# gpi-pwr.net
KiCad netlist of a schematic drawn in EAGLE
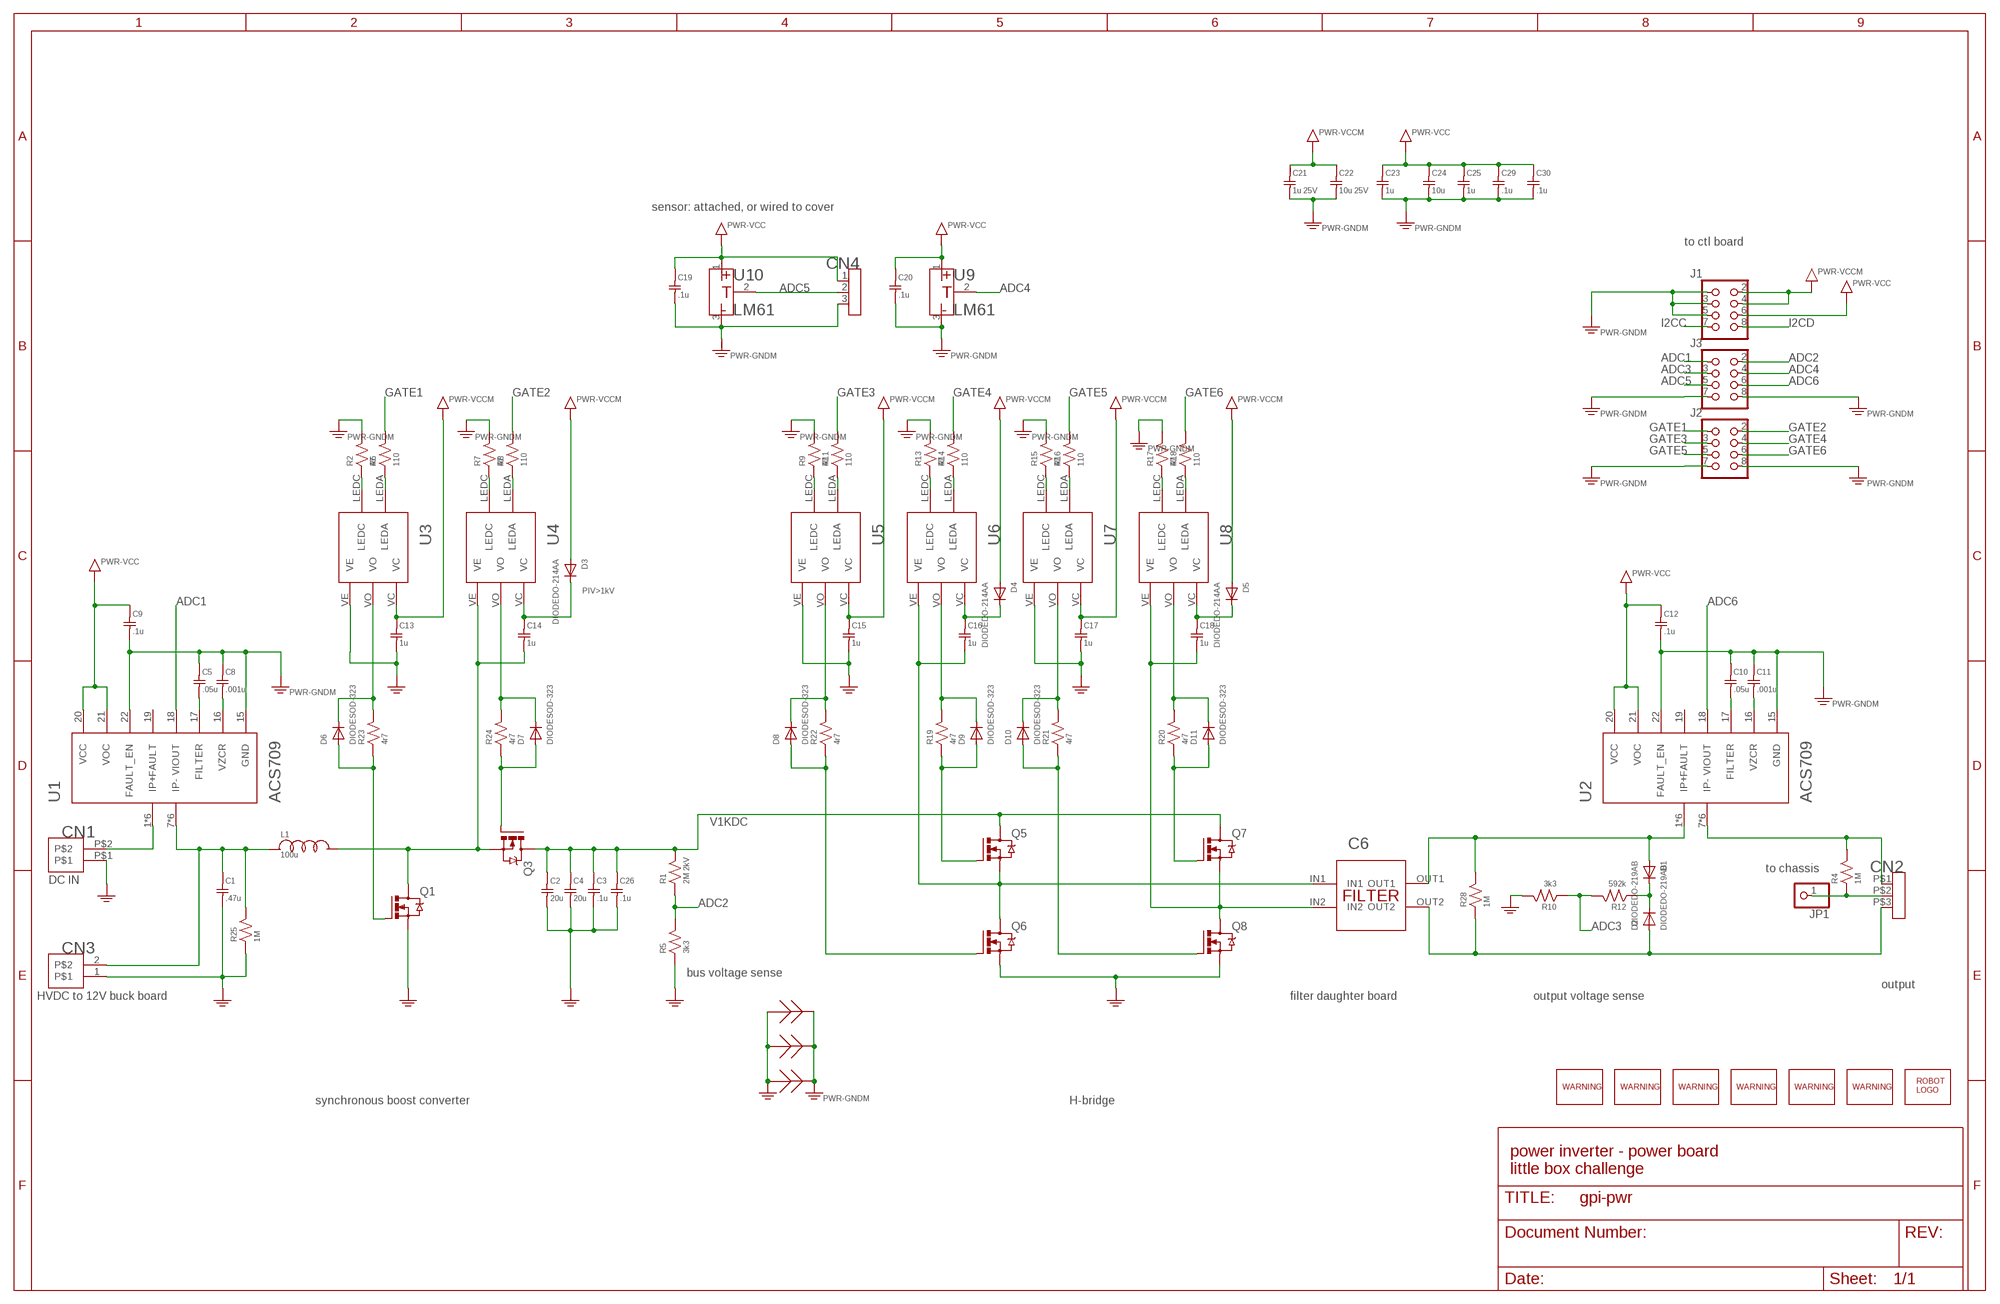
[diagram p0: schematic, sheet 1]

(export (version "E")
  (design (tool "Eeschema 10.0.6"))
  (components
    (comp (ref "C1")
      (value ".47u")
      (footprint "eagle-import:R46KI333000N1M")
      (libsource (lib "eagle-import") (part "CR46KI333000N1M"))
    )
    (comp (ref "C2")
      (value "20u")
      (footprint "eagle-import:MKP1848S62010JY5F")
      (libsource (lib "eagle-import") (part "CMKP1848S62010JY5F"))
    )
    (comp (ref "C3")
      (value ".1u")
      (footprint "eagle-import:SMD2220")
      (libsource (lib "eagle-import") (part "C2220"))
    )
    (comp (ref "C4")
      (value "20u")
      (footprint "eagle-import:MKP1848S62010JY5F")
      (libsource (lib "eagle-import") (part "CMKP1848S62010JY5F"))
    )
    (comp (ref "C5")
      (value ".05u")
      (footprint "eagle-import:SMD0603")
      (libsource (lib "eagle-import") (part "C0603"))
    )
    (comp (ref "C6")
      (value "FILTER")
      (footprint "eagle-import:FILTER-B4R0")
      (libsource (lib "eagle-import") (part "FILTER"))
    )
    (comp (ref "C8")
      (value ".001u")
      (footprint "eagle-import:SMD0603")
      (libsource (lib "eagle-import") (part "C0603"))
    )
    (comp (ref "C9")
      (value ".1u")
      (footprint "eagle-import:SMD0603")
      (libsource (lib "eagle-import") (part "C0603"))
    )
    (comp (ref "C10")
      (value ".05u")
      (footprint "eagle-import:SMD0603")
      (libsource (lib "eagle-import") (part "C0603"))
    )
    (comp (ref "C11")
      (value ".001u")
      (footprint "eagle-import:SMD0603")
      (libsource (lib "eagle-import") (part "C0603"))
    )
    (comp (ref "C12")
      (value ".1u")
      (footprint "eagle-import:SMD0603")
      (libsource (lib "eagle-import") (part "C0603"))
    )
    (comp (ref "C13")
      (value "1u")
      (footprint "eagle-import:SMD0603")
      (libsource (lib "eagle-import") (part "C0603"))
    )
    (comp (ref "C14")
      (value "1u")
      (footprint "eagle-import:SMD0603")
      (libsource (lib "eagle-import") (part "C0603"))
    )
    (comp (ref "C15")
      (value "1u")
      (footprint "eagle-import:SMD0603")
      (libsource (lib "eagle-import") (part "C0603"))
    )
    (comp (ref "C16")
      (value "1u")
      (footprint "eagle-import:SMD0603")
      (libsource (lib "eagle-import") (part "C0603"))
    )
    (comp (ref "C17")
      (value "1u")
      (footprint "eagle-import:SMD0603")
      (libsource (lib "eagle-import") (part "C0603"))
    )
    (comp (ref "C18")
      (value "1u")
      (footprint "eagle-import:SMD0603")
      (libsource (lib "eagle-import") (part "C0603"))
    )
    (comp (ref "C19")
      (value ".1u")
      (footprint "eagle-import:SMD0603")
      (libsource (lib "eagle-import") (part "C0603"))
    )
    (comp (ref "C20")
      (value ".1u")
      (footprint "eagle-import:SMD0603")
      (libsource (lib "eagle-import") (part "C0603"))
    )
    (comp (ref "C21")
      (value "1u 25V")
      (footprint "eagle-import:SMD0603")
      (libsource (lib "eagle-import") (part "C0603"))
    )
    (comp (ref "C22")
      (value "10u 25V")
      (footprint "eagle-import:SMD0603")
      (libsource (lib "eagle-import") (part "C0603"))
    )
    (comp (ref "C23")
      (value "1u")
      (footprint "eagle-import:SMD0603")
      (libsource (lib "eagle-import") (part "C0603"))
    )
    (comp (ref "C24")
      (value "10u")
      (footprint "eagle-import:SMD0603")
      (libsource (lib "eagle-import") (part "C0603"))
    )
    (comp (ref "C25")
      (value "1u")
      (footprint "eagle-import:SMD0603")
      (libsource (lib "eagle-import") (part "C0603"))
    )
    (comp (ref "C26")
      (value ".1u")
      (footprint "eagle-import:SMD2220")
      (libsource (lib "eagle-import") (part "C2220"))
    )
    (comp (ref "C29")
      (value ".1u")
      (footprint "eagle-import:SMD0603")
      (libsource (lib "eagle-import") (part "C0603"))
    )
    (comp (ref "C30")
      (value ".1u")
      (footprint "eagle-import:SMD0603")
      (libsource (lib "eagle-import") (part "C0603"))
    )
    (comp (ref "CN1")
      (value "HEADER-1X2")
      (footprint "eagle-import:CONN-10AWG-2")
      (libsource (lib "eagle-import") (part "HEADER-1X2"))
    )
    (comp (ref "CN2")
      (value "HEADER-3X1")
      (footprint "eagle-import:CONN-10AWG-3")
      (libsource (lib "eagle-import") (part "HEADER-3X1"))
    )
    (comp (ref "CN3")
      (value "HEADER-1X2.4")
      (footprint "eagle-import:HEADER-1X2-THM-WIDE")
      (libsource (lib "eagle-import") (part "HEADER-1X2.4"))
    )
    (comp (ref "CN4")
      (value "HEADER-3X12MM")
      (footprint "eagle-import:HEADER-3X1-2SMD")
      (libsource (lib "eagle-import") (part "HEADER-3X12MM"))
    )
    (comp (ref "D1")
      (value "DIODEDO-219AB")
      (footprint "eagle-import:DO-219AB")
      (libsource (lib "eagle-import") (part "DIODEDO-219AB"))
    )
    (comp (ref "D2")
      (value "DIODEDO-219AB")
      (footprint "eagle-import:DO-219AB")
      (libsource (lib "eagle-import") (part "DIODEDO-219AB"))
    )
    (comp (ref "D3")
      (value "DIODEDO-214AA")
      (footprint "eagle-import:DO-214AA")
      (libsource (lib "eagle-import") (part "DIODEDO-214AA"))
    )
    (comp (ref "D4")
      (value "DIODEDO-214AA")
      (footprint "eagle-import:DO-214AA")
      (libsource (lib "eagle-import") (part "DIODEDO-214AA"))
    )
    (comp (ref "D5")
      (value "DIODEDO-214AA")
      (footprint "eagle-import:DO-214AA")
      (libsource (lib "eagle-import") (part "DIODEDO-214AA"))
    )
    (comp (ref "D6")
      (value "DIODESOD-323")
      (footprint "eagle-import:SOD-323")
      (libsource (lib "eagle-import") (part "DIODESOD-323"))
    )
    (comp (ref "D7")
      (value "DIODESOD-323")
      (footprint "eagle-import:SOD-323")
      (libsource (lib "eagle-import") (part "DIODESOD-323"))
    )
    (comp (ref "D8")
      (value "DIODESOD-323")
      (footprint "eagle-import:SOD-323")
      (libsource (lib "eagle-import") (part "DIODESOD-323"))
    )
    (comp (ref "D9")
      (value "DIODESOD-323")
      (footprint "eagle-import:SOD-323")
      (libsource (lib "eagle-import") (part "DIODESOD-323"))
    )
    (comp (ref "D10")
      (value "DIODESOD-323")
      (footprint "eagle-import:SOD-323")
      (libsource (lib "eagle-import") (part "DIODESOD-323"))
    )
    (comp (ref "D11")
      (value "DIODESOD-323")
      (footprint "eagle-import:SOD-323")
      (libsource (lib "eagle-import") (part "DIODESOD-323"))
    )
    (comp (ref "J1")
      (value "HEADER-2X4")
      (footprint "eagle-import:HEADER-2X04")
      (libsource (lib "eagle-import") (part "HEADER-2X4"))
    )
    (comp (ref "J2")
      (value "HEADER-2X4")
      (footprint "eagle-import:HEADER-2X04")
      (libsource (lib "eagle-import") (part "HEADER-2X4"))
    )
    (comp (ref "J3")
      (value "HEADER-2X4")
      (footprint "eagle-import:HEADER-2X04")
      (libsource (lib "eagle-import") (part "HEADER-2X4"))
    )
    (comp (ref "JP1")
      (value "PINHD-1X1")
      (footprint "eagle-import:1X01")
      (libsource (lib "eagle-import") (part "PINHD-1X1"))
    )
    (comp (ref "L1")
      (value "100u")
      (footprint "eagle-import:AIRD03")
      (libsource (lib "eagle-import") (part "LAIRD03"))
    )
    (comp (ref "Q1")
      (value "C2M0160120D")
      (footprint "eagle-import:TO-247-3-DOWN")
      (libsource (lib "eagle-import") (part "MOSFETTO247REV"))
    )
    (comp (ref "Q3")
      (value "C2M0160120D")
      (footprint "eagle-import:TO-247-3-DOWN")
      (libsource (lib "eagle-import") (part "MOSFETTO247REV"))
    )
    (comp (ref "Q5")
      (value "C2M0160120D")
      (footprint "eagle-import:TO-247-3-DOWN")
      (libsource (lib "eagle-import") (part "MOSFETTO247REV"))
    )
    (comp (ref "Q6")
      (value "C2M0160120D")
      (footprint "eagle-import:TO-247-3-DOWN")
      (libsource (lib "eagle-import") (part "MOSFETTO247REV"))
    )
    (comp (ref "Q7")
      (value "C2M0160120D")
      (footprint "eagle-import:TO-247-3-DOWN")
      (libsource (lib "eagle-import") (part "MOSFETTO247REV"))
    )
    (comp (ref "Q8")
      (value "C2M0160120D")
      (footprint "eagle-import:TO-247-3-DOWN")
      (libsource (lib "eagle-import") (part "MOSFETTO247REV"))
    )
    (comp (ref "R1")
      (value "2M 2kV")
      (footprint "eagle-import:SMD2512")
      (libsource (lib "eagle-import") (part "R2512"))
    )
    (comp (ref "R2")
      (value "47")
      (footprint "eagle-import:SMD0603")
      (libsource (lib "eagle-import") (part "R0603"))
    )
    (comp (ref "R4")
      (value "1M")
      (footprint "eagle-import:SMD1206")
      (libsource (lib "eagle-import") (part "R1206"))
    )
    (comp (ref "R5")
      (value "3k3")
      (footprint "eagle-import:SMD0603")
      (libsource (lib "eagle-import") (part "R0603"))
    )
    (comp (ref "R6")
      (value "110")
      (footprint "eagle-import:SMD0603")
      (libsource (lib "eagle-import") (part "R0603"))
    )
    (comp (ref "R7")
      (value "47")
      (footprint "eagle-import:SMD0603")
      (libsource (lib "eagle-import") (part "R0603"))
    )
    (comp (ref "R8")
      (value "110")
      (footprint "eagle-import:SMD0603")
      (libsource (lib "eagle-import") (part "R0603"))
    )
    (comp (ref "R9")
      (value "47")
      (footprint "eagle-import:SMD0603")
      (libsource (lib "eagle-import") (part "R0603"))
    )
    (comp (ref "R10")
      (value "3k3")
      (footprint "eagle-import:SMD0603")
      (libsource (lib "eagle-import") (part "R0603"))
    )
    (comp (ref "R11")
      (value "110")
      (footprint "eagle-import:SMD0603")
      (libsource (lib "eagle-import") (part "R0603"))
    )
    (comp (ref "R12")
      (value "592k")
      (footprint "eagle-import:SMD1206")
      (libsource (lib "eagle-import") (part "R1206"))
    )
    (comp (ref "R13")
      (value "47")
      (footprint "eagle-import:SMD0603")
      (libsource (lib "eagle-import") (part "R0603"))
    )
    (comp (ref "R14")
      (value "110")
      (footprint "eagle-import:SMD0603")
      (libsource (lib "eagle-import") (part "R0603"))
    )
    (comp (ref "R15")
      (value "47")
      (footprint "eagle-import:SMD0603")
      (libsource (lib "eagle-import") (part "R0603"))
    )
    (comp (ref "R16")
      (value "110")
      (footprint "eagle-import:SMD0603")
      (libsource (lib "eagle-import") (part "R0603"))
    )
    (comp (ref "R17")
      (value "47")
      (footprint "eagle-import:SMD0603")
      (libsource (lib "eagle-import") (part "R0603"))
    )
    (comp (ref "R18")
      (value "110")
      (footprint "eagle-import:SMD0603")
      (libsource (lib "eagle-import") (part "R0603"))
    )
    (comp (ref "R19")
      (value "4r7")
      (footprint "eagle-import:SMD0508")
      (libsource (lib "eagle-import") (part "RSMD0508"))
    )
    (comp (ref "R20")
      (value "4r7")
      (footprint "eagle-import:SMD0508")
      (libsource (lib "eagle-import") (part "RSMD0508"))
    )
    (comp (ref "R21")
      (value "4r7")
      (footprint "eagle-import:SMD0508")
      (libsource (lib "eagle-import") (part "RSMD0508"))
    )
    (comp (ref "R22")
      (value "4r7")
      (footprint "eagle-import:SMD0508")
      (libsource (lib "eagle-import") (part "RSMD0508"))
    )
    (comp (ref "R23")
      (value "4r7")
      (footprint "eagle-import:SMD0508")
      (libsource (lib "eagle-import") (part "RSMD0508"))
    )
    (comp (ref "R24")
      (value "4r7")
      (footprint "eagle-import:SMD0508")
      (libsource (lib "eagle-import") (part "RSMD0508"))
    )
    (comp (ref "R25")
      (value "1M")
      (footprint "eagle-import:SMD1206")
      (libsource (lib "eagle-import") (part "R1206"))
    )
    (comp (ref "R28")
      (value "1M")
      (footprint "eagle-import:SMD1206")
      (libsource (lib "eagle-import") (part "R1206"))
    )
    (comp (ref "U$1")
      (value "ROBOTMAN-LOGO")
      (footprint "eagle-import:ROBOTMAN-LOGO")
      (libsource (lib "eagle-import") (part "ROBOTMAN-LOGO"))
    )
    (comp (ref "U$2")
      (value "SYMBOL-WARNING")
      (footprint "eagle-import:SYMBOL-WARNING")
      (libsource (lib "eagle-import") (part "SYMBOL-WARNING"))
    )
    (comp (ref "U$3")
      (value "SYMBOL-WARNING")
      (footprint "eagle-import:SYMBOL-WARNING")
      (libsource (lib "eagle-import") (part "SYMBOL-WARNING"))
    )
    (comp (ref "U$4")
      (value "SYMBOL-WARNING")
      (footprint "eagle-import:SYMBOL-WARNING")
      (libsource (lib "eagle-import") (part "SYMBOL-WARNING"))
    )
    (comp (ref "U$5")
      (value "SYMBOL-WARNING")
      (footprint "eagle-import:SYMBOL-WARNING")
      (libsource (lib "eagle-import") (part "SYMBOL-WARNING"))
    )
    (comp (ref "U$6")
      (value "SYMBOL-WARNING")
      (footprint "eagle-import:SYMBOL-WARNING")
      (libsource (lib "eagle-import") (part "SYMBOL-WARNING"))
    )
    (comp (ref "U$7")
      (value "SYMBOL-WARNING")
      (footprint "eagle-import:SYMBOL-WARNING")
      (libsource (lib "eagle-import") (part "SYMBOL-WARNING"))
    )
    (comp (ref "U1")
      (value "ACS709")
      (footprint "eagle-import:QSOP24")
      (libsource (lib "eagle-import") (part "ACS709"))
    )
    (comp (ref "U2")
      (value "ACS709")
      (footprint "eagle-import:QSOP24")
      (libsource (lib "eagle-import") (part "ACS709"))
    )
    (comp (ref "U3")
      (value "ACPL-P346P346")
      (footprint "eagle-import:ACPL-P346")
      (libsource (lib "eagle-import") (part "ACPL-P346P346"))
    )
    (comp (ref "U4")
      (value "ACPL-P346P346")
      (footprint "eagle-import:ACPL-P346")
      (libsource (lib "eagle-import") (part "ACPL-P346P346"))
    )
    (comp (ref "U5")
      (value "ACPL-P346P346")
      (footprint "eagle-import:ACPL-P346")
      (libsource (lib "eagle-import") (part "ACPL-P346P346"))
    )
    (comp (ref "U6")
      (value "ACPL-P346P346")
      (footprint "eagle-import:ACPL-P346")
      (libsource (lib "eagle-import") (part "ACPL-P346P346"))
    )
    (comp (ref "U7")
      (value "ACPL-P346P346")
      (footprint "eagle-import:ACPL-P346")
      (libsource (lib "eagle-import") (part "ACPL-P346P346"))
    )
    (comp (ref "U8")
      (value "ACPL-P346P346")
      (footprint "eagle-import:ACPL-P346")
      (libsource (lib "eagle-import") (part "ACPL-P346P346"))
    )
    (comp (ref "U9")
      (value "LM61")
      (footprint "eagle-import:SOT-23")
      (libsource (lib "eagle-import") (part "TEMPERATURE"))
    )
    (comp (ref "U10")
      (value "LM61")
      (footprint "eagle-import:SOT-23")
      (libsource (lib "eagle-import") (part "TEMPERATURE"))
    )
    (comp (ref "Z1")
      (value "SHORT")
      (footprint "eagle-import:SHORT")
      (libsource (lib "eagle-import") (part "SHORT"))
    )
    (comp (ref "Z2")
      (value "SHORT")
      (footprint "eagle-import:SHORT")
      (libsource (lib "eagle-import") (part "SHORT"))
    )
    (comp (ref "Z3")
      (value "SHORT")
      (footprint "eagle-import:SHORT")
      (libsource (lib "eagle-import") (part "SHORT"))
    )
  )
  (nets
    (net (code "1") (name "/ADC1") (class "Default")
      (node (ref "J3") (pin "1") (pinfunction "P$1_1") (pintype "passive"))
      (node (ref "U1") (pin "18") (pinfunction "VIOUT_18") (pintype "bidirectional"))
    )
    (net (code "2") (name "/ADC2") (class "Default")
      (node (ref "J3") (pin "2") (pinfunction "P$2_2") (pintype "passive"))
      (node (ref "R1") (pin "P$1") (pinfunction "P$1_P$1") (pintype "passive"))
      (node (ref "R5") (pin "2") (pinfunction "P$2_2") (pintype "passive"))
    )
    (net (code "3") (name "/ADC3") (class "Default")
      (node (ref "J3") (pin "3") (pinfunction "P$3_3") (pintype "passive"))
      (node (ref "R10") (pin "1") (pinfunction "P$1_1") (pintype "passive"))
      (node (ref "R12") (pin "2") (pinfunction "P$2_2") (pintype "passive"))
    )
    (net (code "4") (name "/ADC4") (class "Default")
      (node (ref "J3") (pin "4") (pinfunction "P$4_4") (pintype "passive"))
      (node (ref "U9") (pin "2") (pinfunction "OUT_2") (pintype "bidirectional"))
    )
    (net (code "5") (name "/ADC5") (class "Default")
      (node (ref "CN4") (pin "2") (pinfunction "2_2") (pintype "bidirectional"))
      (node (ref "J3") (pin "5") (pinfunction "P$5_5") (pintype "passive"))
      (node (ref "U10") (pin "2") (pinfunction "OUT_2") (pintype "bidirectional"))
    )
    (net (code "6") (name "/ADC6") (class "Default")
      (node (ref "J3") (pin "6") (pinfunction "P$6_6") (pintype "passive"))
      (node (ref "U2") (pin "18") (pinfunction "VIOUT_18") (pintype "bidirectional"))
    )
    (net (code "7") (name "/GATE1") (class "Default")
      (node (ref "J2") (pin "1") (pinfunction "P$1_1") (pintype "passive"))
      (node (ref "R6") (pin "2") (pinfunction "P$2_2") (pintype "passive"))
    )
    (net (code "8") (name "/GATE2") (class "Default")
      (node (ref "J2") (pin "2") (pinfunction "P$2_2") (pintype "passive"))
      (node (ref "R8") (pin "2") (pinfunction "P$2_2") (pintype "passive"))
    )
    (net (code "9") (name "/GATE3") (class "Default")
      (node (ref "J2") (pin "3") (pinfunction "P$3_3") (pintype "passive"))
      (node (ref "R11") (pin "2") (pinfunction "P$2_2") (pintype "passive"))
    )
    (net (code "10") (name "/GATE4") (class "Default")
      (node (ref "J2") (pin "4") (pinfunction "P$4_4") (pintype "passive"))
      (node (ref "R14") (pin "2") (pinfunction "P$2_2") (pintype "passive"))
    )
    (net (code "11") (name "/GATE5") (class "Default")
      (node (ref "J2") (pin "5") (pinfunction "P$5_5") (pintype "passive"))
      (node (ref "R16") (pin "2") (pinfunction "P$2_2") (pintype "passive"))
    )
    (net (code "12") (name "/GATE6") (class "Default")
      (node (ref "J2") (pin "6") (pinfunction "P$6_6") (pintype "passive"))
      (node (ref "R18") (pin "2") (pinfunction "P$2_2") (pintype "passive"))
    )
    (net (code "13") (name "/I2CC") (class "Default")
      (node (ref "J1") (pin "7") (pinfunction "P$7_7") (pintype "passive"))
    )
    (net (code "14") (name "/I2CD") (class "Default")
      (node (ref "J1") (pin "8") (pinfunction "P$8_8") (pintype "passive"))
    )
    (net (code "15") (name "/V1KDC") (class "Default")
      (node (ref "C2") (pin "1A") (pinfunction "P$1_1A") (pintype "passive"))
      (node (ref "C2") (pin "1B") (pinfunction "P$1_1B") (pintype "passive"))
      (node (ref "C26") (pin "P$1") (pinfunction "P$1_P$1") (pintype "passive"))
      (node (ref "C3") (pin "P$1") (pinfunction "P$1_P$1") (pintype "passive"))
      (node (ref "C4") (pin "1A") (pinfunction "P$1_1A") (pintype "passive"))
      (node (ref "C4") (pin "1B") (pinfunction "P$1_1B") (pintype "passive"))
      (node (ref "Q3") (pin "2") (pinfunction "D_2") (pintype "passive"))
      (node (ref "Q5") (pin "2") (pinfunction "D_2") (pintype "passive"))
      (node (ref "Q7") (pin "2") (pinfunction "D_2") (pintype "passive"))
      (node (ref "R1") (pin "P$2") (pinfunction "P$2_P$2") (pintype "passive"))
    )
    (net (code "16") (name "Net-(C5-P$2)") (class "Default")
      (node (ref "C5") (pin "2") (pinfunction "P$2_2") (pintype "passive"))
      (node (ref "U1") (pin "17") (pinfunction "FILTER_17") (pintype "bidirectional"))
    )
    (net (code "17") (name "Net-(C8-P$2)") (class "Default")
      (node (ref "C8") (pin "2") (pinfunction "P$2_2") (pintype "passive"))
      (node (ref "U1") (pin "16") (pinfunction "VZCR_16") (pintype "bidirectional"))
    )
    (net (code "18") (name "Net-(C10-P$2)") (class "Default")
      (node (ref "C10") (pin "2") (pinfunction "P$2_2") (pintype "passive"))
      (node (ref "U2") (pin "17") (pinfunction "FILTER_17") (pintype "bidirectional"))
    )
    (net (code "19") (name "Net-(C11-P$2)") (class "Default")
      (node (ref "C11") (pin "2") (pinfunction "P$2_2") (pintype "passive"))
      (node (ref "U2") (pin "16") (pinfunction "VZCR_16") (pintype "bidirectional"))
    )
    (net (code "20") (name "Net-(C14-P$1)") (class "Default")
      (node (ref "C14") (pin "1") (pinfunction "P$1_1") (pintype "passive"))
      (node (ref "D3") (pin "C") (pinfunction "C_C") (pintype "passive"))
      (node (ref "U4") (pin "VC") (pinfunction "VC_VC") (pintype "bidirectional"))
    )
    (net (code "21") (name "Net-(C14-P$2)") (class "Default")
      (node (ref "C14") (pin "2") (pinfunction "P$2_2") (pintype "passive"))
      (node (ref "L1") (pin "P$2") (pinfunction "P$2_P$2") (pintype "passive"))
      (node (ref "Q1") (pin "2") (pinfunction "D_2") (pintype "passive"))
      (node (ref "Q3") (pin "3") (pinfunction "S_3") (pintype "passive"))
      (node (ref "U4") (pin "VE") (pinfunction "VE_VE") (pintype "bidirectional"))
    )
    (net (code "22") (name "Net-(C16-P$1)") (class "Default")
      (node (ref "C16") (pin "1") (pinfunction "P$1_1") (pintype "passive"))
      (node (ref "D4") (pin "C") (pinfunction "C_C") (pintype "passive"))
      (node (ref "U6") (pin "VC") (pinfunction "VC_VC") (pintype "bidirectional"))
    )
    (net (code "23") (name "Net-(C16-P$2)") (class "Default")
      (node (ref "C16") (pin "2") (pinfunction "P$2_2") (pintype "passive"))
      (node (ref "C6") (pin "IN1") (pinfunction "IN1_IN1") (pintype "bidirectional"))
      (node (ref "Q5") (pin "3") (pinfunction "S_3") (pintype "passive"))
      (node (ref "Q6") (pin "2") (pinfunction "D_2") (pintype "passive"))
      (node (ref "U6") (pin "VE") (pinfunction "VE_VE") (pintype "bidirectional"))
    )
    (net (code "24") (name "Net-(C18-P$1)") (class "Default")
      (node (ref "C18") (pin "1") (pinfunction "P$1_1") (pintype "passive"))
      (node (ref "D5") (pin "C") (pinfunction "C_C") (pintype "passive"))
      (node (ref "U8") (pin "VC") (pinfunction "VC_VC") (pintype "bidirectional"))
    )
    (net (code "25") (name "Net-(C18-P$2)") (class "Default")
      (node (ref "C18") (pin "2") (pinfunction "P$2_2") (pintype "passive"))
      (node (ref "C6") (pin "IN2") (pinfunction "IN2_IN2") (pintype "bidirectional"))
      (node (ref "Q7") (pin "3") (pinfunction "S_3") (pintype "passive"))
      (node (ref "Q8") (pin "2") (pinfunction "D_2") (pintype "passive"))
      (node (ref "U8") (pin "VE") (pinfunction "VE_VE") (pintype "bidirectional"))
    )
    (net (code "26") (name "Net-(CN1-PadP$2)") (class "Default")
      (node (ref "CN1") (pin "P$2") (pinfunction "P$2_P$2") (pintype "bidirectional"))
      (node (ref "U1") (pin "1") (pinfunction "IP+_1") (pintype "bidirectional"))
      (node (ref "U1") (pin "2") (pinfunction "IP+_2") (pintype "bidirectional"))
      (node (ref "U1") (pin "3") (pinfunction "IP+_3") (pintype "bidirectional"))
      (node (ref "U1") (pin "4") (pinfunction "IP+_4") (pintype "bidirectional"))
      (node (ref "U1") (pin "5") (pinfunction "IP+_5") (pintype "bidirectional"))
      (node (ref "U1") (pin "6") (pinfunction "IP+_6") (pintype "bidirectional"))
    )
    (net (code "27") (name "Net-(CN2-1)") (class "Default")
      (node (ref "CN2") (pin "P$1") (pinfunction "1_P$1") (pintype "bidirectional"))
      (node (ref "R4") (pin "2") (pinfunction "P$2_2") (pintype "passive"))
      (node (ref "U2") (pin "10") (pinfunction "IP-_10") (pintype "bidirectional"))
      (node (ref "U2") (pin "11") (pinfunction "IP-_11") (pintype "bidirectional"))
      (node (ref "U2") (pin "12") (pinfunction "IP-_12") (pintype "bidirectional"))
      (node (ref "U2") (pin "7") (pinfunction "IP-_7") (pintype "bidirectional"))
      (node (ref "U2") (pin "8") (pinfunction "IP-_8") (pintype "bidirectional"))
      (node (ref "U2") (pin "9") (pinfunction "IP-_9") (pintype "bidirectional"))
    )
    (net (code "28") (name "Net-(CN2-2)") (class "Default")
      (node (ref "CN2") (pin "P$2") (pinfunction "2_P$2") (pintype "bidirectional"))
      (node (ref "JP1") (pin "1") (pinfunction "1_1") (pintype "passive"))
      (node (ref "R4") (pin "1") (pinfunction "P$1_1") (pintype "passive"))
    )
    (net (code "29") (name "Net-(CN2-3)") (class "Default")
      (node (ref "C6") (pin "OUT2") (pinfunction "OUT2_OUT2") (pintype "bidirectional"))
      (node (ref "CN2") (pin "P$3") (pinfunction "3_P$3") (pintype "bidirectional"))
      (node (ref "D2") (pin "A") (pinfunction "A_A") (pintype "passive"))
      (node (ref "R28") (pin "1") (pinfunction "P$1_1") (pintype "passive"))
    )
    (net (code "30") (name "Net-(CN3-P$2)") (class "Default")
      (node (ref "C1") (pin "P$1") (pinfunction "P$1_P$1") (pintype "passive"))
      (node (ref "CN3") (pin "2") (pinfunction "P$2_2") (pintype "bidirectional"))
      (node (ref "L1") (pin "P$1") (pinfunction "P$1_P$1") (pintype "passive"))
      (node (ref "R25") (pin "2") (pinfunction "P$2_2") (pintype "passive"))
      (node (ref "U1") (pin "10") (pinfunction "IP-_10") (pintype "bidirectional"))
      (node (ref "U1") (pin "11") (pinfunction "IP-_11") (pintype "bidirectional"))
      (node (ref "U1") (pin "12") (pinfunction "IP-_12") (pintype "bidirectional"))
      (node (ref "U1") (pin "7") (pinfunction "IP-_7") (pintype "bidirectional"))
      (node (ref "U1") (pin "8") (pinfunction "IP-_8") (pintype "bidirectional"))
      (node (ref "U1") (pin "9") (pinfunction "IP-_9") (pintype "bidirectional"))
    )
    (net (code "31") (name "Net-(D6-PadC)") (class "Default")
      (node (ref "D6") (pin "C") (pinfunction "C_C") (pintype "passive"))
      (node (ref "R23") (pin "P$2") (pinfunction "P$2_P$2") (pintype "passive"))
      (node (ref "U3") (pin "VO") (pinfunction "VO_VO") (pintype "bidirectional"))
    )
    (net (code "32") (name "Net-(D7-PadC)") (class "Default")
      (node (ref "D7") (pin "C") (pinfunction "C_C") (pintype "passive"))
      (node (ref "R24") (pin "P$2") (pinfunction "P$2_P$2") (pintype "passive"))
      (node (ref "U4") (pin "VO") (pinfunction "VO_VO") (pintype "bidirectional"))
    )
    (net (code "33") (name "Net-(D8-PadC)") (class "Default")
      (node (ref "D8") (pin "C") (pinfunction "C_C") (pintype "passive"))
      (node (ref "R22") (pin "P$2") (pinfunction "P$2_P$2") (pintype "passive"))
      (node (ref "U5") (pin "VO") (pinfunction "VO_VO") (pintype "bidirectional"))
    )
    (net (code "34") (name "Net-(D9-PadC)") (class "Default")
      (node (ref "D9") (pin "C") (pinfunction "C_C") (pintype "passive"))
      (node (ref "R19") (pin "P$2") (pinfunction "P$2_P$2") (pintype "passive"))
      (node (ref "U6") (pin "VO") (pinfunction "VO_VO") (pintype "bidirectional"))
    )
    (net (code "35") (name "Net-(D10-PadC)") (class "Default")
      (node (ref "D10") (pin "C") (pinfunction "C_C") (pintype "passive"))
      (node (ref "R21") (pin "P$2") (pinfunction "P$2_P$2") (pintype "passive"))
      (node (ref "U7") (pin "VO") (pinfunction "VO_VO") (pintype "bidirectional"))
    )
    (net (code "36") (name "Net-(D11-PadC)") (class "Default")
      (node (ref "D11") (pin "C") (pinfunction "C_C") (pintype "passive"))
      (node (ref "R20") (pin "P$2") (pinfunction "P$2_P$2") (pintype "passive"))
      (node (ref "U8") (pin "VO") (pinfunction "VO_VO") (pintype "bidirectional"))
    )
    (net (code "37") (name "Net-(Q1-G)") (class "Default")
      (node (ref "D6") (pin "A") (pinfunction "A_A") (pintype "passive"))
      (node (ref "Q1") (pin "1") (pinfunction "G_1") (pintype "passive"))
      (node (ref "R23") (pin "P$1") (pinfunction "P$1_P$1") (pintype "passive"))
    )
    (net (code "38") (name "Net-(Q3-G)") (class "Default")
      (node (ref "D7") (pin "A") (pinfunction "A_A") (pintype "passive"))
      (node (ref "Q3") (pin "1") (pinfunction "G_1") (pintype "passive"))
      (node (ref "R24") (pin "P$1") (pinfunction "P$1_P$1") (pintype "passive"))
    )
    (net (code "39") (name "Net-(Q5-G)") (class "Default")
      (node (ref "D9") (pin "A") (pinfunction "A_A") (pintype "passive"))
      (node (ref "Q5") (pin "1") (pinfunction "G_1") (pintype "passive"))
      (node (ref "R19") (pin "P$1") (pinfunction "P$1_P$1") (pintype "passive"))
    )
    (net (code "40") (name "Net-(Q6-G)") (class "Default")
      (node (ref "D8") (pin "A") (pinfunction "A_A") (pintype "passive"))
      (node (ref "Q6") (pin "1") (pinfunction "G_1") (pintype "passive"))
      (node (ref "R22") (pin "P$1") (pinfunction "P$1_P$1") (pintype "passive"))
    )
    (net (code "41") (name "Net-(Q7-G)") (class "Default")
      (node (ref "D11") (pin "A") (pinfunction "A_A") (pintype "passive"))
      (node (ref "Q7") (pin "1") (pinfunction "G_1") (pintype "passive"))
      (node (ref "R20") (pin "P$1") (pinfunction "P$1_P$1") (pintype "passive"))
    )
    (net (code "42") (name "Net-(Q8-G)") (class "Default")
      (node (ref "D10") (pin "A") (pinfunction "A_A") (pintype "passive"))
      (node (ref "Q8") (pin "1") (pinfunction "G_1") (pintype "passive"))
      (node (ref "R21") (pin "P$1") (pinfunction "P$1_P$1") (pintype "passive"))
    )
    (net (code "43") (name "Net-(R2-P$1)") (class "Default")
      (node (ref "R2") (pin "1") (pinfunction "P$1_1") (pintype "passive"))
      (node (ref "U3") (pin "LEDC") (pinfunction "LEDC_LEDC") (pintype "bidirectional"))
    )
    (net (code "44") (name "Net-(R6-P$1)") (class "Default")
      (node (ref "R6") (pin "1") (pinfunction "P$1_1") (pintype "passive"))
      (node (ref "U3") (pin "LEDA") (pinfunction "LEDA_LEDA") (pintype "bidirectional"))
    )
    (net (code "45") (name "Net-(R7-P$1)") (class "Default")
      (node (ref "R7") (pin "1") (pinfunction "P$1_1") (pintype "passive"))
      (node (ref "U4") (pin "LEDC") (pinfunction "LEDC_LEDC") (pintype "bidirectional"))
    )
    (net (code "46") (name "Net-(R8-P$1)") (class "Default")
      (node (ref "R8") (pin "1") (pinfunction "P$1_1") (pintype "passive"))
      (node (ref "U4") (pin "LEDA") (pinfunction "LEDA_LEDA") (pintype "bidirectional"))
    )
    (net (code "47") (name "Net-(R9-P$1)") (class "Default")
      (node (ref "R9") (pin "1") (pinfunction "P$1_1") (pintype "passive"))
      (node (ref "U5") (pin "LEDC") (pinfunction "LEDC_LEDC") (pintype "bidirectional"))
    )
    (net (code "48") (name "Net-(R11-P$1)") (class "Default")
      (node (ref "R11") (pin "1") (pinfunction "P$1_1") (pintype "passive"))
      (node (ref "U5") (pin "LEDA") (pinfunction "LEDA_LEDA") (pintype "bidirectional"))
    )
    (net (code "49") (name "Net-(R12-P$1)") (class "Default")
      (node (ref "D1") (pin "C") (pinfunction "C_C") (pintype "passive"))
      (node (ref "D2") (pin "C") (pinfunction "C_C") (pintype "passive"))
      (node (ref "R12") (pin "1") (pinfunction "P$1_1") (pintype "passive"))
    )
    (net (code "50") (name "Net-(R13-P$1)") (class "Default")
      (node (ref "R13") (pin "1") (pinfunction "P$1_1") (pintype "passive"))
      (node (ref "U6") (pin "LEDC") (pinfunction "LEDC_LEDC") (pintype "bidirectional"))
    )
    (net (code "51") (name "Net-(R14-P$1)") (class "Default")
      (node (ref "R14") (pin "1") (pinfunction "P$1_1") (pintype "passive"))
      (node (ref "U6") (pin "LEDA") (pinfunction "LEDA_LEDA") (pintype "bidirectional"))
    )
    (net (code "52") (name "Net-(R15-P$1)") (class "Default")
      (node (ref "R15") (pin "1") (pinfunction "P$1_1") (pintype "passive"))
      (node (ref "U7") (pin "LEDC") (pinfunction "LEDC_LEDC") (pintype "bidirectional"))
    )
    (net (code "53") (name "Net-(R16-P$1)") (class "Default")
      (node (ref "R16") (pin "1") (pinfunction "P$1_1") (pintype "passive"))
      (node (ref "U7") (pin "LEDA") (pinfunction "LEDA_LEDA") (pintype "bidirectional"))
    )
    (net (code "54") (name "Net-(R17-P$1)") (class "Default")
      (node (ref "R17") (pin "1") (pinfunction "P$1_1") (pintype "passive"))
      (node (ref "U8") (pin "LEDC") (pinfunction "LEDC_LEDC") (pintype "bidirectional"))
    )
    (net (code "55") (name "Net-(R18-P$1)") (class "Default")
      (node (ref "R18") (pin "1") (pinfunction "P$1_1") (pintype "passive"))
      (node (ref "U8") (pin "LEDA") (pinfunction "LEDA_LEDA") (pintype "bidirectional"))
    )
    (net (code "56") (name "Net-(R28-P$2)") (class "Default")
      (node (ref "C6") (pin "OUT1") (pinfunction "OUT1_OUT1") (pintype "bidirectional"))
      (node (ref "D1") (pin "A") (pinfunction "A_A") (pintype "passive"))
      (node (ref "R28") (pin "2") (pinfunction "P$2_2") (pintype "passive"))
      (node (ref "U2") (pin "1") (pinfunction "IP+_1") (pintype "bidirectional"))
      (node (ref "U2") (pin "2") (pinfunction "IP+_2") (pintype "bidirectional"))
      (node (ref "U2") (pin "3") (pinfunction "IP+_3") (pintype "bidirectional"))
      (node (ref "U2") (pin "4") (pinfunction "IP+_4") (pintype "bidirectional"))
      (node (ref "U2") (pin "5") (pinfunction "IP+_5") (pintype "bidirectional"))
      (node (ref "U2") (pin "6") (pinfunction "IP+_6") (pintype "bidirectional"))
    )
    (net (code "57") (name "PWR-GND") (class "Default")
      (node (ref "C1") (pin "P$2") (pinfunction "P$2_P$2") (pintype "passive"))
      (node (ref "C13") (pin "2") (pinfunction "P$2_2") (pintype "passive"))
      (node (ref "C15") (pin "2") (pinfunction "P$2_2") (pintype "passive"))
      (node (ref "C17") (pin "2") (pinfunction "P$2_2") (pintype "passive"))
      (node (ref "C2") (pin "2A") (pinfunction "P$2_2A") (pintype "passive"))
      (node (ref "C2") (pin "2B") (pinfunction "P$2_2B") (pintype "passive"))
      (node (ref "C26") (pin "P$2") (pinfunction "P$2_P$2") (pintype "passive"))
      (node (ref "C3") (pin "P$2") (pinfunction "P$2_P$2") (pintype "passive"))
      (node (ref "C4") (pin "2A") (pinfunction "P$2_2A") (pintype "passive"))
      (node (ref "C4") (pin "2B") (pinfunction "P$2_2B") (pintype "passive"))
      (node (ref "CN1") (pin "P$1") (pinfunction "P$1_P$1") (pintype "bidirectional"))
      (node (ref "CN3") (pin "1") (pinfunction "P$1_1") (pintype "bidirectional"))
      (node (ref "Q1") (pin "3") (pinfunction "S_3") (pintype "passive"))
      (node (ref "Q6") (pin "3") (pinfunction "S_3") (pintype "passive"))
      (node (ref "Q8") (pin "3") (pinfunction "S_3") (pintype "passive"))
      (node (ref "R10") (pin "2") (pinfunction "P$2_2") (pintype "passive"))
      (node (ref "R25") (pin "1") (pinfunction "P$1_1") (pintype "passive"))
      (node (ref "R5") (pin "1") (pinfunction "P$1_1") (pintype "passive"))
      (node (ref "U3") (pin "VE") (pinfunction "VE_VE") (pintype "bidirectional"))
      (node (ref "U5") (pin "VE") (pinfunction "VE_VE") (pintype "bidirectional"))
      (node (ref "U7") (pin "VE") (pinfunction "VE_VE") (pintype "bidirectional"))
      (node (ref "Z1") (pin "P$1") (pinfunction "P$1_P$1") (pintype "bidirectional"))
      (node (ref "Z2") (pin "P$1") (pinfunction "P$1_P$1") (pintype "bidirectional"))
      (node (ref "Z3") (pin "P$1") (pinfunction "P$1_P$1") (pintype "bidirectional"))
    )
    (net (code "58") (name "PWR-GNDM") (class "Default")
      (node (ref "C10") (pin "1") (pinfunction "P$1_1") (pintype "passive"))
      (node (ref "C11") (pin "1") (pinfunction "P$1_1") (pintype "passive"))
      (node (ref "C12") (pin "2") (pinfunction "P$2_2") (pintype "passive"))
      (node (ref "C19") (pin "2") (pinfunction "P$2_2") (pintype "passive"))
      (node (ref "C20") (pin "2") (pinfunction "P$2_2") (pintype "passive"))
      (node (ref "C21") (pin "2") (pinfunction "P$2_2") (pintype "passive"))
      (node (ref "C22") (pin "2") (pinfunction "P$2_2") (pintype "passive"))
      (node (ref "C23") (pin "2") (pinfunction "P$2_2") (pintype "passive"))
      (node (ref "C24") (pin "2") (pinfunction "P$2_2") (pintype "passive"))
      (node (ref "C25") (pin "2") (pinfunction "P$2_2") (pintype "passive"))
      (node (ref "C29") (pin "2") (pinfunction "P$2_2") (pintype "passive"))
      (node (ref "C30") (pin "2") (pinfunction "P$2_2") (pintype "passive"))
      (node (ref "C5") (pin "1") (pinfunction "P$1_1") (pintype "passive"))
      (node (ref "C8") (pin "1") (pinfunction "P$1_1") (pintype "passive"))
      (node (ref "C9") (pin "2") (pinfunction "P$2_2") (pintype "passive"))
      (node (ref "CN4") (pin "3") (pinfunction "3_3") (pintype "bidirectional"))
      (node (ref "J1") (pin "1") (pinfunction "P$1_1") (pintype "passive"))
      (node (ref "J1") (pin "3") (pinfunction "P$3_3") (pintype "passive"))
      (node (ref "J1") (pin "5") (pinfunction "P$5_5") (pintype "passive"))
      (node (ref "J2") (pin "7") (pinfunction "P$7_7") (pintype "passive"))
      (node (ref "J2") (pin "8") (pinfunction "P$8_8") (pintype "passive"))
      (node (ref "J3") (pin "7") (pinfunction "P$7_7") (pintype "passive"))
      (node (ref "J3") (pin "8") (pinfunction "P$8_8") (pintype "passive"))
      (node (ref "R13") (pin "2") (pinfunction "P$2_2") (pintype "passive"))
      (node (ref "R15") (pin "2") (pinfunction "P$2_2") (pintype "passive"))
      (node (ref "R17") (pin "2") (pinfunction "P$2_2") (pintype "passive"))
      (node (ref "R2") (pin "2") (pinfunction "P$2_2") (pintype "passive"))
      (node (ref "R7") (pin "2") (pinfunction "P$2_2") (pintype "passive"))
      (node (ref "R9") (pin "2") (pinfunction "P$2_2") (pintype "passive"))
      (node (ref "U1") (pin "15") (pinfunction "GND_15") (pintype "bidirectional"))
      (node (ref "U1") (pin "22") (pinfunction "FAULT_EN_22") (pintype "bidirectional"))
      (node (ref "U10") (pin "3") (pinfunction "G_3") (pintype "bidirectional"))
      (node (ref "U2") (pin "15") (pinfunction "GND_15") (pintype "bidirectional"))
      (node (ref "U2") (pin "22") (pinfunction "FAULT_EN_22") (pintype "bidirectional"))
      (node (ref "U9") (pin "3") (pinfunction "G_3") (pintype "bidirectional"))
      (node (ref "Z1") (pin "P$2") (pinfunction "P$2_P$2") (pintype "bidirectional"))
      (node (ref "Z2") (pin "P$2") (pinfunction "P$2_P$2") (pintype "bidirectional"))
      (node (ref "Z3") (pin "P$2") (pinfunction "P$2_P$2") (pintype "bidirectional"))
    )
    (net (code "59") (name "PWR-VCC") (class "Default")
      (node (ref "C12") (pin "1") (pinfunction "P$1_1") (pintype "passive"))
      (node (ref "C19") (pin "1") (pinfunction "P$1_1") (pintype "passive"))
      (node (ref "C20") (pin "1") (pinfunction "P$1_1") (pintype "passive"))
      (node (ref "C23") (pin "1") (pinfunction "P$1_1") (pintype "passive"))
      (node (ref "C24") (pin "1") (pinfunction "P$1_1") (pintype "passive"))
      (node (ref "C25") (pin "1") (pinfunction "P$1_1") (pintype "passive"))
      (node (ref "C29") (pin "1") (pinfunction "P$1_1") (pintype "passive"))
      (node (ref "C30") (pin "1") (pinfunction "P$1_1") (pintype "passive"))
      (node (ref "C9") (pin "1") (pinfunction "P$1_1") (pintype "passive"))
      (node (ref "CN4") (pin "1") (pinfunction "1_1") (pintype "bidirectional"))
      (node (ref "J1") (pin "6") (pinfunction "P$6_6") (pintype "passive"))
      (node (ref "U1") (pin "20") (pinfunction "VCC_20") (pintype "bidirectional"))
      (node (ref "U1") (pin "21") (pinfunction "VOC_21") (pintype "bidirectional"))
      (node (ref "U10") (pin "1") (pinfunction "V_1") (pintype "bidirectional"))
      (node (ref "U2") (pin "20") (pinfunction "VCC_20") (pintype "bidirectional"))
      (node (ref "U2") (pin "21") (pinfunction "VOC_21") (pintype "bidirectional"))
      (node (ref "U9") (pin "1") (pinfunction "V_1") (pintype "bidirectional"))
    )
    (net (code "60") (name "PWR-VCCM") (class "Default")
      (node (ref "C13") (pin "1") (pinfunction "P$1_1") (pintype "passive"))
      (node (ref "C15") (pin "1") (pinfunction "P$1_1") (pintype "passive"))
      (node (ref "C17") (pin "1") (pinfunction "P$1_1") (pintype "passive"))
      (node (ref "C21") (pin "1") (pinfunction "P$1_1") (pintype "passive"))
      (node (ref "C22") (pin "1") (pinfunction "P$1_1") (pintype "passive"))
      (node (ref "D3") (pin "A") (pinfunction "A_A") (pintype "passive"))
      (node (ref "D4") (pin "A") (pinfunction "A_A") (pintype "passive"))
      (node (ref "D5") (pin "A") (pinfunction "A_A") (pintype "passive"))
      (node (ref "J1") (pin "2") (pinfunction "P$2_2") (pintype "passive"))
      (node (ref "J1") (pin "4") (pinfunction "P$4_4") (pintype "passive"))
      (node (ref "U3") (pin "VC") (pinfunction "VC_VC") (pintype "bidirectional"))
      (node (ref "U5") (pin "VC") (pinfunction "VC_VC") (pintype "bidirectional"))
      (node (ref "U7") (pin "VC") (pinfunction "VC_VC") (pintype "bidirectional"))
    )
    (net (code "61") (name "unconnected-(U1-FAULT-Pad19)") (class "Default")
      (node (ref "U1") (pin "19") (pinfunction "FAULT_19") (pintype "bidirectional"))
    )
    (net (code "62") (name "unconnected-(U2-FAULT-Pad19)") (class "Default")
      (node (ref "U2") (pin "19") (pinfunction "FAULT_19") (pintype "bidirectional"))
    )
  )
)
